# Cap_Sensor_hand.net
KiCad netlist of a schematic drawn in Altium Designer
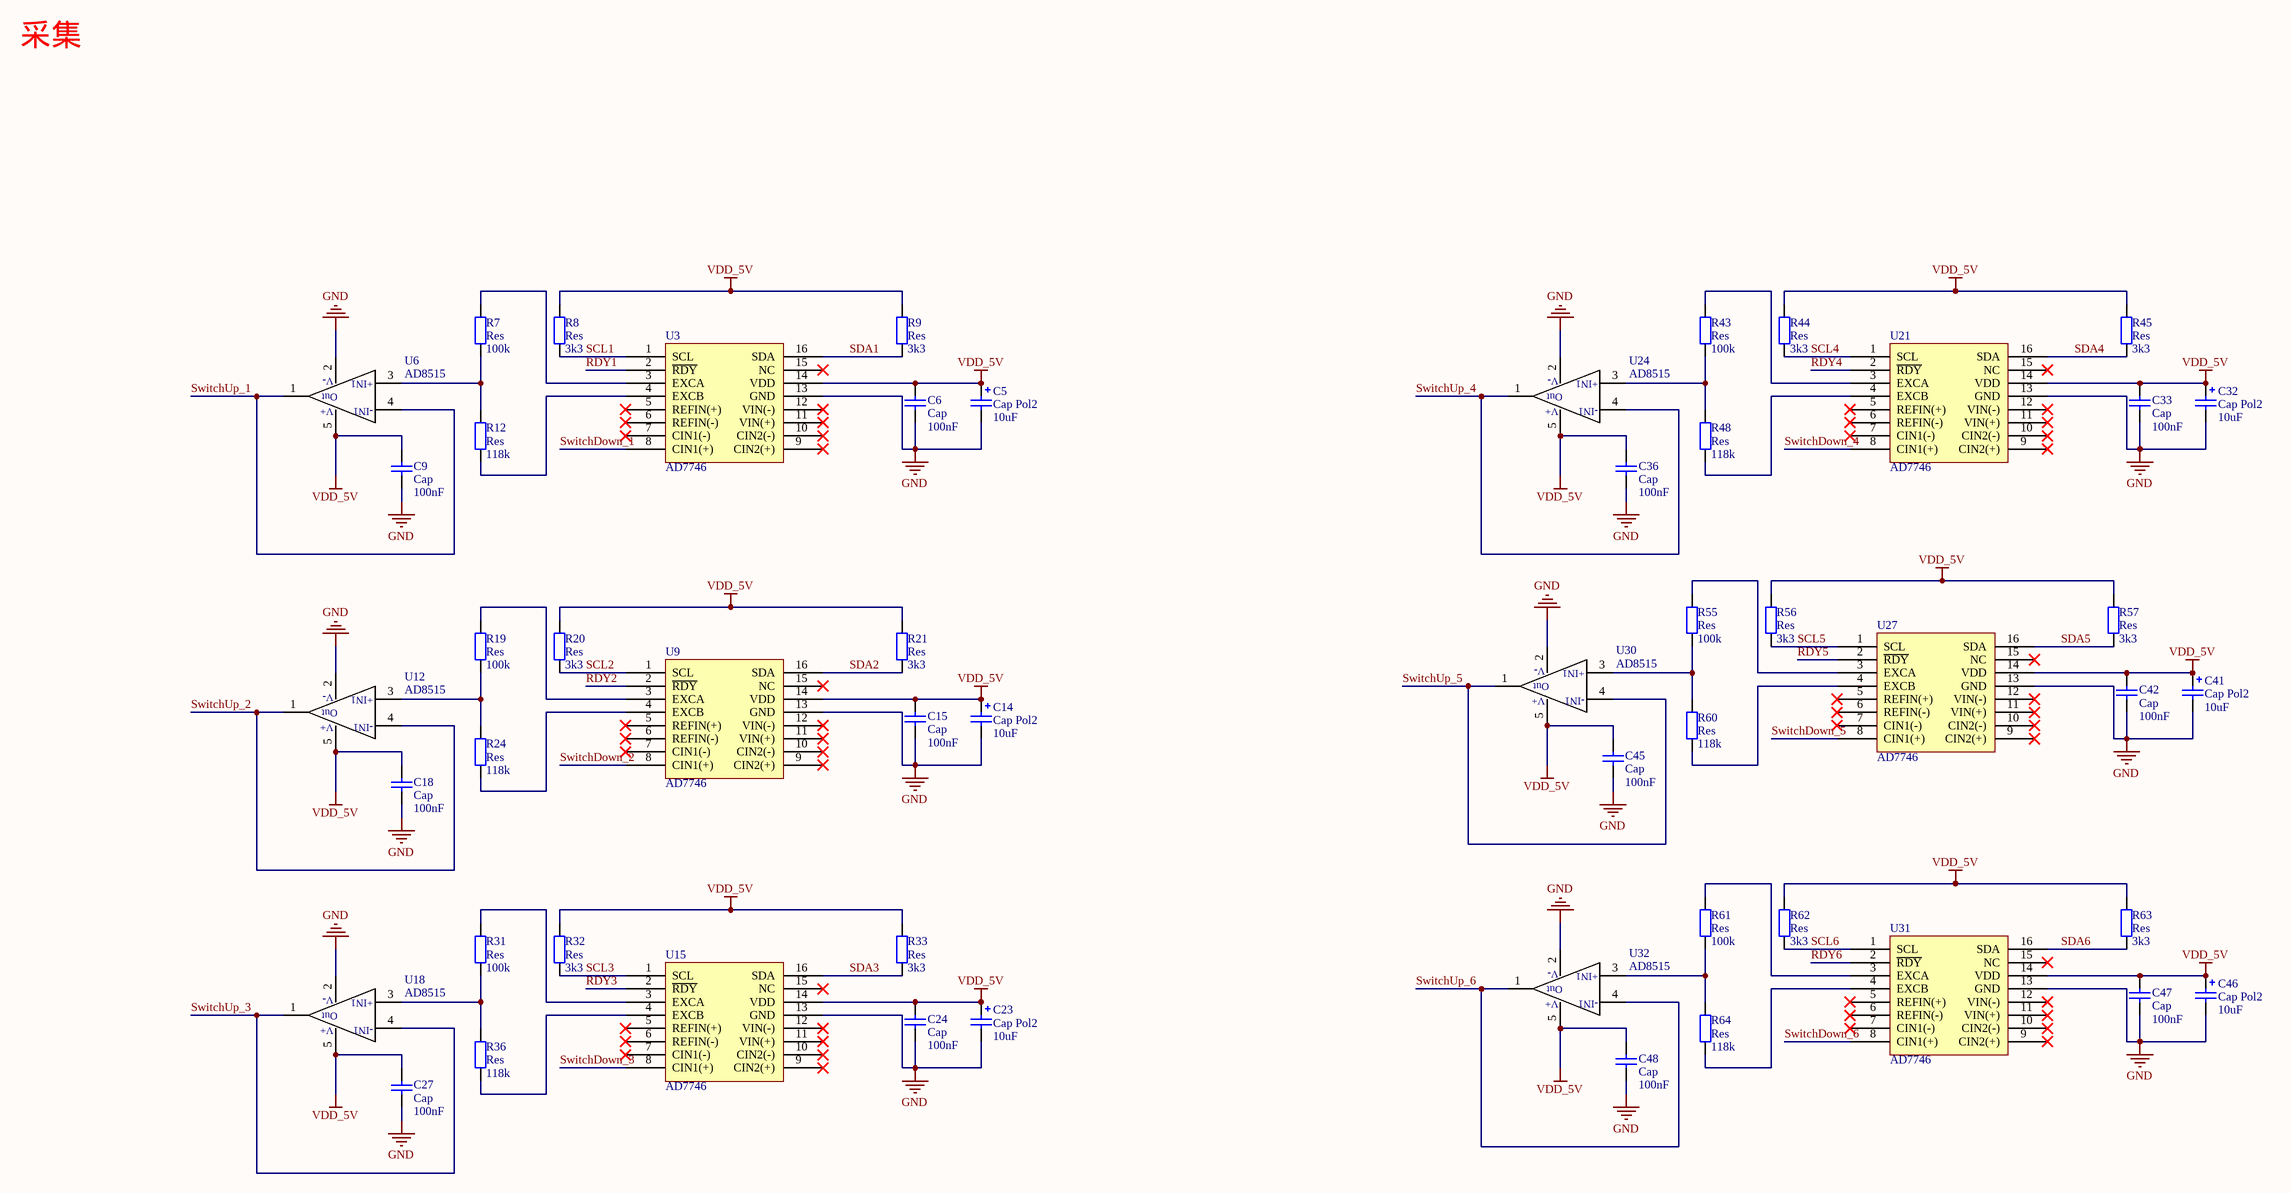
[diagram p0: Cap_Sensor_hand.SchDoc]

(export (version "E")
  (design (tool "Eeschema 10.0.6"))
  (components
    (comp (ref "C5")
      (value "Cap Pol2")
      (footprint "Cap-TA")
      (description "Polarized Capacitor (Axial)")
      (fields (field (name "ALTIUM_VALUE") "10uF") (field (name "PUBLISHER") "Altium Limited"))
      (libsource (lib "YD-LibrarySCH") (part "Cap Pol2"))
    )
    (comp (ref "C6")
      (value "Cap")
      (footprint "0805C")
      (description "Capacitor")
      (fields (field (name "ALTIUM_VALUE") "100nF") (field (name "PUBLISHER") "Altium Limited"))
      (libsource (lib "YD-LibrarySCH") (part "Cap"))
    )
    (comp (ref "C9")
      (value "Cap")
      (footprint "0805C")
      (description "Capacitor")
      (fields (field (name "ALTIUM_VALUE") "100nF") (field (name "PUBLISHER") "Altium Limited"))
      (libsource (lib "YD-LibrarySCH") (part "Cap"))
    )
    (comp (ref "C14")
      (value "Cap Pol2")
      (footprint "Cap-TA")
      (description "Polarized Capacitor (Axial)")
      (fields (field (name "ALTIUM_VALUE") "10uF") (field (name "PUBLISHER") "Altium Limited"))
      (libsource (lib "YD-LibrarySCH") (part "Cap Pol2"))
    )
    (comp (ref "C15")
      (value "Cap")
      (footprint "0805C")
      (description "Capacitor")
      (fields (field (name "ALTIUM_VALUE") "100nF") (field (name "PUBLISHER") "Altium Limited"))
      (libsource (lib "YD-LibrarySCH") (part "Cap"))
    )
    (comp (ref "C18")
      (value "Cap")
      (footprint "0805C")
      (description "Capacitor")
      (fields (field (name "ALTIUM_VALUE") "100nF") (field (name "PUBLISHER") "Altium Limited"))
      (libsource (lib "YD-LibrarySCH") (part "Cap"))
    )
    (comp (ref "C23")
      (value "Cap Pol2")
      (footprint "Cap-TA")
      (description "Polarized Capacitor (Axial)")
      (fields (field (name "ALTIUM_VALUE") "10uF") (field (name "PUBLISHER") "Altium Limited"))
      (libsource (lib "YD-LibrarySCH") (part "Cap Pol2"))
    )
    (comp (ref "C24")
      (value "Cap")
      (footprint "0805C")
      (description "Capacitor")
      (fields (field (name "ALTIUM_VALUE") "100nF") (field (name "PUBLISHER") "Altium Limited"))
      (libsource (lib "YD-LibrarySCH") (part "Cap"))
    )
    (comp (ref "C27")
      (value "Cap")
      (footprint "0805C")
      (description "Capacitor")
      (fields (field (name "ALTIUM_VALUE") "100nF") (field (name "PUBLISHER") "Altium Limited"))
      (libsource (lib "YD-LibrarySCH") (part "Cap"))
    )
    (comp (ref "C32")
      (value "Cap Pol2")
      (footprint "Cap-TA")
      (description "Polarized Capacitor (Axial)")
      (fields (field (name "ALTIUM_VALUE") "10uF") (field (name "PUBLISHER") "Altium Limited"))
      (libsource (lib "YD-LibrarySCH") (part "Cap Pol2"))
    )
    (comp (ref "C33")
      (value "Cap")
      (footprint "0805C")
      (description "Capacitor")
      (fields (field (name "ALTIUM_VALUE") "100nF") (field (name "PUBLISHER") "Altium Limited"))
      (libsource (lib "YD-LibrarySCH") (part "Cap"))
    )
    (comp (ref "C36")
      (value "Cap")
      (footprint "0805C")
      (description "Capacitor")
      (fields (field (name "ALTIUM_VALUE") "100nF") (field (name "PUBLISHER") "Altium Limited"))
      (libsource (lib "YD-LibrarySCH") (part "Cap"))
    )
    (comp (ref "C41")
      (value "Cap Pol2")
      (footprint "Cap-TA")
      (description "Polarized Capacitor (Axial)")
      (fields (field (name "ALTIUM_VALUE") "10uF") (field (name "PUBLISHER") "Altium Limited"))
      (libsource (lib "YD-LibrarySCH") (part "Cap Pol2"))
    )
    (comp (ref "C42")
      (value "Cap")
      (footprint "0805C")
      (description "Capacitor")
      (fields (field (name "ALTIUM_VALUE") "100nF") (field (name "PUBLISHER") "Altium Limited"))
      (libsource (lib "YD-LibrarySCH") (part "Cap"))
    )
    (comp (ref "C45")
      (value "Cap")
      (footprint "0805C")
      (description "Capacitor")
      (fields (field (name "ALTIUM_VALUE") "100nF") (field (name "PUBLISHER") "Altium Limited"))
      (libsource (lib "YD-LibrarySCH") (part "Cap"))
    )
    (comp (ref "C46")
      (value "Cap Pol2")
      (footprint "Cap-TA")
      (description "Polarized Capacitor (Axial)")
      (fields (field (name "ALTIUM_VALUE") "10uF") (field (name "PUBLISHER") "Altium Limited"))
      (libsource (lib "YD-LibrarySCH") (part "Cap Pol2"))
    )
    (comp (ref "C47")
      (value "Cap")
      (footprint "0805C")
      (description "Capacitor")
      (fields (field (name "ALTIUM_VALUE") "100nF") (field (name "PUBLISHER") "Altium Limited"))
      (libsource (lib "YD-LibrarySCH") (part "Cap"))
    )
    (comp (ref "C48")
      (value "Cap")
      (footprint "0805C")
      (description "Capacitor")
      (fields (field (name "ALTIUM_VALUE") "100nF") (field (name "PUBLISHER") "Altium Limited"))
      (libsource (lib "YD-LibrarySCH") (part "Cap"))
    )
    (comp (ref "R7")
      (value "Res")
      (footprint "0805R")
      (description "Resistor")
      (fields (field (name "ALTIUM_VALUE") "100k") (field (name "PUBLISHER") "Altium Limited"))
      (libsource (lib "YD-LibrarySCH") (part "Res"))
    )
    (comp (ref "R8")
      (value "Res")
      (footprint "0805R")
      (description "Resistor")
      (fields (field (name "ALTIUM_VALUE") "3k3") (field (name "PUBLISHER") "Altium Limited"))
      (libsource (lib "") (part "Res_1"))
    )
    (comp (ref "R9")
      (value "Res")
      (footprint "0805R")
      (description "Resistor")
      (fields (field (name "ALTIUM_VALUE") "3k3") (field (name "PUBLISHER") "Altium Limited"))
      (libsource (lib "") (part "Res_1"))
    )
    (comp (ref "R12")
      (value "Res")
      (footprint "0805R")
      (description "Resistor")
      (fields (field (name "ALTIUM_VALUE") "118k") (field (name "PUBLISHER") "Altium Limited"))
      (libsource (lib "YD-LibrarySCH") (part "Res"))
    )
    (comp (ref "R19")
      (value "Res")
      (footprint "0805R")
      (description "Resistor")
      (fields (field (name "ALTIUM_VALUE") "100k") (field (name "PUBLISHER") "Altium Limited"))
      (libsource (lib "YD-LibrarySCH") (part "Res"))
    )
    (comp (ref "R20")
      (value "Res")
      (footprint "0805R")
      (description "Resistor")
      (fields (field (name "ALTIUM_VALUE") "3k3") (field (name "PUBLISHER") "Altium Limited"))
      (libsource (lib "") (part "Res_1"))
    )
    (comp (ref "R21")
      (value "Res")
      (footprint "0805R")
      (description "Resistor")
      (fields (field (name "ALTIUM_VALUE") "3k3") (field (name "PUBLISHER") "Altium Limited"))
      (libsource (lib "") (part "Res_1"))
    )
    (comp (ref "R24")
      (value "Res")
      (footprint "0805R")
      (description "Resistor")
      (fields (field (name "ALTIUM_VALUE") "118k") (field (name "PUBLISHER") "Altium Limited"))
      (libsource (lib "YD-LibrarySCH") (part "Res"))
    )
    (comp (ref "R31")
      (value "Res")
      (footprint "0805R")
      (description "Resistor")
      (fields (field (name "ALTIUM_VALUE") "100k") (field (name "PUBLISHER") "Altium Limited"))
      (libsource (lib "YD-LibrarySCH") (part "Res"))
    )
    (comp (ref "R32")
      (value "Res")
      (footprint "0805R")
      (description "Resistor")
      (fields (field (name "ALTIUM_VALUE") "3k3") (field (name "PUBLISHER") "Altium Limited"))
      (libsource (lib "") (part "Res_1"))
    )
    (comp (ref "R33")
      (value "Res")
      (footprint "0805R")
      (description "Resistor")
      (fields (field (name "ALTIUM_VALUE") "3k3") (field (name "PUBLISHER") "Altium Limited"))
      (libsource (lib "") (part "Res_1"))
    )
    (comp (ref "R36")
      (value "Res")
      (footprint "0805R")
      (description "Resistor")
      (fields (field (name "ALTIUM_VALUE") "118k") (field (name "PUBLISHER") "Altium Limited"))
      (libsource (lib "YD-LibrarySCH") (part "Res"))
    )
    (comp (ref "R43")
      (value "Res")
      (footprint "0805R")
      (description "Resistor")
      (fields (field (name "ALTIUM_VALUE") "100k") (field (name "PUBLISHER") "Altium Limited"))
      (libsource (lib "YD-LibrarySCH") (part "Res"))
    )
    (comp (ref "R44")
      (value "Res")
      (footprint "0805R")
      (description "Resistor")
      (fields (field (name "ALTIUM_VALUE") "3k3") (field (name "PUBLISHER") "Altium Limited"))
      (libsource (lib "") (part "Res_1"))
    )
    (comp (ref "R45")
      (value "Res")
      (footprint "0805R")
      (description "Resistor")
      (fields (field (name "ALTIUM_VALUE") "3k3") (field (name "PUBLISHER") "Altium Limited"))
      (libsource (lib "") (part "Res_1"))
    )
    (comp (ref "R48")
      (value "Res")
      (footprint "0805R")
      (description "Resistor")
      (fields (field (name "ALTIUM_VALUE") "118k") (field (name "PUBLISHER") "Altium Limited"))
      (libsource (lib "YD-LibrarySCH") (part "Res"))
    )
    (comp (ref "R55")
      (value "Res")
      (footprint "0805R")
      (description "Resistor")
      (fields (field (name "ALTIUM_VALUE") "100k") (field (name "PUBLISHER") "Altium Limited"))
      (libsource (lib "YD-LibrarySCH") (part "Res"))
    )
    (comp (ref "R56")
      (value "Res")
      (footprint "0805R")
      (description "Resistor")
      (fields (field (name "ALTIUM_VALUE") "3k3") (field (name "PUBLISHER") "Altium Limited"))
      (libsource (lib "") (part "Res_1"))
    )
    (comp (ref "R57")
      (value "Res")
      (footprint "0805R")
      (description "Resistor")
      (fields (field (name "ALTIUM_VALUE") "3k3") (field (name "PUBLISHER") "Altium Limited"))
      (libsource (lib "") (part "Res_1"))
    )
    (comp (ref "R60")
      (value "Res")
      (footprint "0805R")
      (description "Resistor")
      (fields (field (name "ALTIUM_VALUE") "118k") (field (name "PUBLISHER") "Altium Limited"))
      (libsource (lib "YD-LibrarySCH") (part "Res"))
    )
    (comp (ref "R61")
      (value "Res")
      (footprint "0805R")
      (description "Resistor")
      (fields (field (name "ALTIUM_VALUE") "100k") (field (name "PUBLISHER") "Altium Limited"))
      (libsource (lib "YD-LibrarySCH") (part "Res"))
    )
    (comp (ref "R62")
      (value "Res")
      (footprint "0805R")
      (description "Resistor")
      (fields (field (name "ALTIUM_VALUE") "3k3") (field (name "PUBLISHER") "Altium Limited"))
      (libsource (lib "") (part "Res_1"))
    )
    (comp (ref "R63")
      (value "Res")
      (footprint "0805R")
      (description "Resistor")
      (fields (field (name "ALTIUM_VALUE") "3k3") (field (name "PUBLISHER") "Altium Limited"))
      (libsource (lib "") (part "Res_1"))
    )
    (comp (ref "R64")
      (value "Res")
      (footprint "0805R")
      (description "Resistor")
      (fields (field (name "ALTIUM_VALUE") "118k") (field (name "PUBLISHER") "Altium Limited"))
      (libsource (lib "YD-LibrarySCH") (part "Res"))
    )
    (comp (ref "U3") (value "AD7746") (footprint "TSSOP16") (libsource (lib "YD-LibrarySCH") (part "AD7746")))
    (comp (ref "U6") (value "AD8515") (footprint "sot23-5") (libsource (lib "YD-LibrarySCH") (part "AD8515")))
    (comp (ref "U9") (value "AD7746") (footprint "TSSOP16") (libsource (lib "YD-LibrarySCH") (part "AD7746")))
    (comp (ref "U12")
      (value "AD8515")
      (footprint "sot23-5")
      (libsource (lib "YD-LibrarySCH") (part "AD8515"))
    )
    (comp (ref "U15")
      (value "AD7746")
      (footprint "TSSOP16")
      (libsource (lib "YD-LibrarySCH") (part "AD7746"))
    )
    (comp (ref "U18")
      (value "AD8515")
      (footprint "sot23-5")
      (libsource (lib "YD-LibrarySCH") (part "AD8515"))
    )
    (comp (ref "U21")
      (value "AD7746")
      (footprint "TSSOP16")
      (libsource (lib "YD-LibrarySCH") (part "AD7746"))
    )
    (comp (ref "U24")
      (value "AD8515")
      (footprint "sot23-5")
      (libsource (lib "YD-LibrarySCH") (part "AD8515"))
    )
    (comp (ref "U27")
      (value "AD7746")
      (footprint "TSSOP16")
      (libsource (lib "YD-LibrarySCH") (part "AD7746"))
    )
    (comp (ref "U30")
      (value "AD8515")
      (footprint "sot23-5")
      (libsource (lib "YD-LibrarySCH") (part "AD8515"))
    )
    (comp (ref "U31")
      (value "AD7746")
      (footprint "TSSOP16")
      (libsource (lib "YD-LibrarySCH") (part "AD7746"))
    )
    (comp (ref "U32")
      (value "AD8515")
      (footprint "sot23-5")
      (libsource (lib "YD-LibrarySCH") (part "AD8515"))
    )
  )
  (nets
    (net (code "1") (name "/RDY1") (class "Default")
      (node (ref "U3") (pin "2") (pinfunction "~{RDY}_2") (pintype "passive"))
    )
    (net (code "2") (name "/RDY2") (class "Default")
      (node (ref "U9") (pin "2") (pinfunction "~{RDY}_2") (pintype "passive"))
    )
    (net (code "3") (name "/RDY3") (class "Default")
      (node (ref "U15") (pin "2") (pinfunction "~{RDY}_2") (pintype "passive"))
    )
    (net (code "4") (name "/RDY4") (class "Default")
      (node (ref "U21") (pin "2") (pinfunction "~{RDY}_2") (pintype "passive"))
    )
    (net (code "5") (name "/RDY5") (class "Default")
      (node (ref "U27") (pin "2") (pinfunction "~{RDY}_2") (pintype "passive"))
    )
    (net (code "6") (name "/RDY6") (class "Default")
      (node (ref "U31") (pin "2") (pinfunction "~{RDY}_2") (pintype "passive"))
    )
    (net (code "7") (name "/SCL1") (class "Default")
      (node (ref "R8") (pin "1") (pinfunction "1_1") (pintype "passive"))
      (node (ref "U3") (pin "1") (pinfunction "SCL_1") (pintype "passive"))
    )
    (net (code "8") (name "/SCL2") (class "Default")
      (node (ref "R20") (pin "1") (pinfunction "1_1") (pintype "passive"))
      (node (ref "U9") (pin "1") (pinfunction "SCL_1") (pintype "passive"))
    )
    (net (code "9") (name "/SCL3") (class "Default")
      (node (ref "R32") (pin "1") (pinfunction "1_1") (pintype "passive"))
      (node (ref "U15") (pin "1") (pinfunction "SCL_1") (pintype "passive"))
    )
    (net (code "10") (name "/SCL4") (class "Default")
      (node (ref "R44") (pin "1") (pinfunction "1_1") (pintype "passive"))
      (node (ref "U21") (pin "1") (pinfunction "SCL_1") (pintype "passive"))
    )
    (net (code "11") (name "/SCL5") (class "Default")
      (node (ref "R56") (pin "1") (pinfunction "1_1") (pintype "passive"))
      (node (ref "U27") (pin "1") (pinfunction "SCL_1") (pintype "passive"))
    )
    (net (code "12") (name "/SCL6") (class "Default")
      (node (ref "R62") (pin "1") (pinfunction "1_1") (pintype "passive"))
      (node (ref "U31") (pin "1") (pinfunction "SCL_1") (pintype "passive"))
    )
    (net (code "13") (name "/SDA1") (class "Default")
      (node (ref "R9") (pin "1") (pinfunction "1_1") (pintype "passive"))
      (node (ref "U3") (pin "16") (pinfunction "SDA_16") (pintype "passive"))
    )
    (net (code "14") (name "/SDA2") (class "Default")
      (node (ref "R21") (pin "1") (pinfunction "1_1") (pintype "passive"))
      (node (ref "U9") (pin "16") (pinfunction "SDA_16") (pintype "passive"))
    )
    (net (code "15") (name "/SDA3") (class "Default")
      (node (ref "R33") (pin "1") (pinfunction "1_1") (pintype "passive"))
      (node (ref "U15") (pin "16") (pinfunction "SDA_16") (pintype "passive"))
    )
    (net (code "16") (name "/SDA4") (class "Default")
      (node (ref "R45") (pin "1") (pinfunction "1_1") (pintype "passive"))
      (node (ref "U21") (pin "16") (pinfunction "SDA_16") (pintype "passive"))
    )
    (net (code "17") (name "/SDA5") (class "Default")
      (node (ref "R57") (pin "1") (pinfunction "1_1") (pintype "passive"))
      (node (ref "U27") (pin "16") (pinfunction "SDA_16") (pintype "passive"))
    )
    (net (code "18") (name "/SDA6") (class "Default")
      (node (ref "R63") (pin "1") (pinfunction "1_1") (pintype "passive"))
      (node (ref "U31") (pin "16") (pinfunction "SDA_16") (pintype "passive"))
    )
    (net (code "19") (name "/SwitchDown_1") (class "Default")
      (node (ref "U3") (pin "8") (pinfunction "CIN1(+)_8") (pintype "passive"))
    )
    (net (code "20") (name "/SwitchDown_2") (class "Default")
      (node (ref "U9") (pin "8") (pinfunction "CIN1(+)_8") (pintype "passive"))
    )
    (net (code "21") (name "/SwitchDown_3") (class "Default")
      (node (ref "U15") (pin "8") (pinfunction "CIN1(+)_8") (pintype "passive"))
    )
    (net (code "22") (name "/SwitchDown_4") (class "Default")
      (node (ref "U21") (pin "8") (pinfunction "CIN1(+)_8") (pintype "passive"))
    )
    (net (code "23") (name "/SwitchDown_5") (class "Default")
      (node (ref "U27") (pin "8") (pinfunction "CIN1(+)_8") (pintype "passive"))
    )
    (net (code "24") (name "/SwitchDown_6") (class "Default")
      (node (ref "U31") (pin "8") (pinfunction "CIN1(+)_8") (pintype "passive"))
    )
    (net (code "25") (name "/SwitchUp_1") (class "Default")
      (node (ref "U6") (pin "1") (pinfunction "Out1_1") (pintype "passive"))
      (node (ref "U6") (pin "4") (pinfunction "-IN_4") (pintype "passive"))
    )
    (net (code "26") (name "/SwitchUp_2") (class "Default")
      (node (ref "U12") (pin "1") (pinfunction "Out1_1") (pintype "passive"))
      (node (ref "U12") (pin "4") (pinfunction "-IN_4") (pintype "passive"))
    )
    (net (code "27") (name "/SwitchUp_3") (class "Default")
      (node (ref "U18") (pin "1") (pinfunction "Out1_1") (pintype "passive"))
      (node (ref "U18") (pin "4") (pinfunction "-IN_4") (pintype "passive"))
    )
    (net (code "28") (name "/SwitchUp_4") (class "Default")
      (node (ref "U24") (pin "1") (pinfunction "Out1_1") (pintype "passive"))
      (node (ref "U24") (pin "4") (pinfunction "-IN_4") (pintype "passive"))
    )
    (net (code "29") (name "/SwitchUp_5") (class "Default")
      (node (ref "U30") (pin "1") (pinfunction "Out1_1") (pintype "passive"))
      (node (ref "U30") (pin "4") (pinfunction "-IN_4") (pintype "passive"))
    )
    (net (code "30") (name "/SwitchUp_6") (class "Default")
      (node (ref "U32") (pin "1") (pinfunction "Out1_1") (pintype "passive"))
      (node (ref "U32") (pin "4") (pinfunction "-IN_4") (pintype "passive"))
    )
    (net (code "32") (name "GND") (class "Default")
      (node (ref "C14") (pin "2") (pinfunction "2_2") (pintype "passive"))
      (node (ref "C15") (pin "1") (pinfunction "1_1") (pintype "passive"))
      (node (ref "C18") (pin "1") (pinfunction "1_1") (pintype "passive"))
      (node (ref "C23") (pin "2") (pinfunction "2_2") (pintype "passive"))
      (node (ref "C24") (pin "1") (pinfunction "1_1") (pintype "passive"))
      (node (ref "C27") (pin "1") (pinfunction "1_1") (pintype "passive"))
      (node (ref "C32") (pin "2") (pinfunction "2_2") (pintype "passive"))
      (node (ref "C33") (pin "1") (pinfunction "1_1") (pintype "passive"))
      (node (ref "C36") (pin "1") (pinfunction "1_1") (pintype "passive"))
      (node (ref "C41") (pin "2") (pinfunction "2_2") (pintype "passive"))
      (node (ref "C42") (pin "1") (pinfunction "1_1") (pintype "passive"))
      (node (ref "C45") (pin "1") (pinfunction "1_1") (pintype "passive"))
      (node (ref "C46") (pin "2") (pinfunction "2_2") (pintype "passive"))
      (node (ref "C47") (pin "1") (pinfunction "1_1") (pintype "passive"))
      (node (ref "C48") (pin "1") (pinfunction "1_1") (pintype "passive"))
      (node (ref "C5") (pin "2") (pinfunction "2_2") (pintype "passive"))
      (node (ref "C6") (pin "1") (pinfunction "1_1") (pintype "passive"))
      (node (ref "C9") (pin "1") (pinfunction "1_1") (pintype "passive"))
      (node (ref "U12") (pin "2") (pinfunction "V-_2") (pintype "passive"))
      (node (ref "U15") (pin "13") (pinfunction "GND_13") (pintype "passive"))
      (node (ref "U18") (pin "2") (pinfunction "V-_2") (pintype "passive"))
      (node (ref "U21") (pin "13") (pinfunction "GND_13") (pintype "passive"))
      (node (ref "U24") (pin "2") (pinfunction "V-_2") (pintype "passive"))
      (node (ref "U27") (pin "13") (pinfunction "GND_13") (pintype "passive"))
      (node (ref "U3") (pin "13") (pinfunction "GND_13") (pintype "passive"))
      (node (ref "U30") (pin "2") (pinfunction "V-_2") (pintype "passive"))
      (node (ref "U31") (pin "13") (pinfunction "GND_13") (pintype "passive"))
      (node (ref "U32") (pin "2") (pinfunction "V-_2") (pintype "passive"))
      (node (ref "U6") (pin "2") (pinfunction "V-_2") (pintype "passive"))
      (node (ref "U9") (pin "13") (pinfunction "GND_13") (pintype "passive"))
    )
    (net (code "33") (name "Net-(U3-EXCA)") (class "Default")
      (node (ref "R7") (pin "1") (pinfunction "1_1") (pintype "passive"))
      (node (ref "U3") (pin "3") (pinfunction "EXCA_3") (pintype "passive"))
    )
    (net (code "34") (name "Net-(U3-EXCB)") (class "Default")
      (node (ref "R12") (pin "2") (pinfunction "2_2") (pintype "passive"))
      (node (ref "U3") (pin "4") (pinfunction "EXCB_4") (pintype "passive"))
    )
    (net (code "35") (name "Net-(U6-+IN)") (class "Default")
      (node (ref "R12") (pin "1") (pinfunction "1_1") (pintype "passive"))
      (node (ref "R7") (pin "2") (pinfunction "2_2") (pintype "passive"))
      (node (ref "U6") (pin "3") (pinfunction "+IN_3") (pintype "passive"))
    )
    (net (code "36") (name "Net-(U9-EXCA)") (class "Default")
      (node (ref "R19") (pin "1") (pinfunction "1_1") (pintype "passive"))
      (node (ref "U9") (pin "3") (pinfunction "EXCA_3") (pintype "passive"))
    )
    (net (code "37") (name "Net-(U9-EXCB)") (class "Default")
      (node (ref "R24") (pin "2") (pinfunction "2_2") (pintype "passive"))
      (node (ref "U9") (pin "4") (pinfunction "EXCB_4") (pintype "passive"))
    )
    (net (code "38") (name "Net-(U12-+IN)") (class "Default")
      (node (ref "R19") (pin "2") (pinfunction "2_2") (pintype "passive"))
      (node (ref "R24") (pin "1") (pinfunction "1_1") (pintype "passive"))
      (node (ref "U12") (pin "3") (pinfunction "+IN_3") (pintype "passive"))
    )
    (net (code "39") (name "Net-(U15-EXCA)") (class "Default")
      (node (ref "R31") (pin "1") (pinfunction "1_1") (pintype "passive"))
      (node (ref "U15") (pin "3") (pinfunction "EXCA_3") (pintype "passive"))
    )
    (net (code "40") (name "Net-(U15-EXCB)") (class "Default")
      (node (ref "R36") (pin "2") (pinfunction "2_2") (pintype "passive"))
      (node (ref "U15") (pin "4") (pinfunction "EXCB_4") (pintype "passive"))
    )
    (net (code "41") (name "Net-(U18-+IN)") (class "Default")
      (node (ref "R31") (pin "2") (pinfunction "2_2") (pintype "passive"))
      (node (ref "R36") (pin "1") (pinfunction "1_1") (pintype "passive"))
      (node (ref "U18") (pin "3") (pinfunction "+IN_3") (pintype "passive"))
    )
    (net (code "42") (name "Net-(U21-EXCA)") (class "Default")
      (node (ref "R43") (pin "1") (pinfunction "1_1") (pintype "passive"))
      (node (ref "U21") (pin "3") (pinfunction "EXCA_3") (pintype "passive"))
    )
    (net (code "43") (name "Net-(U21-EXCB)") (class "Default")
      (node (ref "R48") (pin "2") (pinfunction "2_2") (pintype "passive"))
      (node (ref "U21") (pin "4") (pinfunction "EXCB_4") (pintype "passive"))
    )
    (net (code "44") (name "Net-(U24-+IN)") (class "Default")
      (node (ref "R43") (pin "2") (pinfunction "2_2") (pintype "passive"))
      (node (ref "R48") (pin "1") (pinfunction "1_1") (pintype "passive"))
      (node (ref "U24") (pin "3") (pinfunction "+IN_3") (pintype "passive"))
    )
    (net (code "45") (name "Net-(U27-EXCA)") (class "Default")
      (node (ref "R55") (pin "1") (pinfunction "1_1") (pintype "passive"))
      (node (ref "U27") (pin "3") (pinfunction "EXCA_3") (pintype "passive"))
    )
    (net (code "46") (name "Net-(U27-EXCB)") (class "Default")
      (node (ref "R60") (pin "2") (pinfunction "2_2") (pintype "passive"))
      (node (ref "U27") (pin "4") (pinfunction "EXCB_4") (pintype "passive"))
    )
    (net (code "47") (name "Net-(U30-+IN)") (class "Default")
      (node (ref "R55") (pin "2") (pinfunction "2_2") (pintype "passive"))
      (node (ref "R60") (pin "1") (pinfunction "1_1") (pintype "passive"))
      (node (ref "U30") (pin "3") (pinfunction "+IN_3") (pintype "passive"))
    )
    (net (code "48") (name "Net-(U31-EXCA)") (class "Default")
      (node (ref "R61") (pin "1") (pinfunction "1_1") (pintype "passive"))
      (node (ref "U31") (pin "3") (pinfunction "EXCA_3") (pintype "passive"))
    )
    (net (code "49") (name "Net-(U31-EXCB)") (class "Default")
      (node (ref "R64") (pin "2") (pinfunction "2_2") (pintype "passive"))
      (node (ref "U31") (pin "4") (pinfunction "EXCB_4") (pintype "passive"))
    )
    (net (code "50") (name "Net-(U32-+IN)") (class "Default")
      (node (ref "R61") (pin "2") (pinfunction "2_2") (pintype "passive"))
      (node (ref "R64") (pin "1") (pinfunction "1_1") (pintype "passive"))
      (node (ref "U32") (pin "3") (pinfunction "+IN_3") (pintype "passive"))
    )
    (net (code "51") (name "VDD_5V") (class "Default")
      (node (ref "C14") (pin "1") (pinfunction "1_1") (pintype "passive"))
      (node (ref "C15") (pin "2") (pinfunction "2_2") (pintype "passive"))
      (node (ref "C18") (pin "2") (pinfunction "2_2") (pintype "passive"))
      (node (ref "C23") (pin "1") (pinfunction "1_1") (pintype "passive"))
      (node (ref "C24") (pin "2") (pinfunction "2_2") (pintype "passive"))
      (node (ref "C27") (pin "2") (pinfunction "2_2") (pintype "passive"))
      (node (ref "C32") (pin "1") (pinfunction "1_1") (pintype "passive"))
      (node (ref "C33") (pin "2") (pinfunction "2_2") (pintype "passive"))
      (node (ref "C36") (pin "2") (pinfunction "2_2") (pintype "passive"))
      (node (ref "C41") (pin "1") (pinfunction "1_1") (pintype "passive"))
      (node (ref "C42") (pin "2") (pinfunction "2_2") (pintype "passive"))
      (node (ref "C45") (pin "2") (pinfunction "2_2") (pintype "passive"))
      (node (ref "C46") (pin "1") (pinfunction "1_1") (pintype "passive"))
      (node (ref "C47") (pin "2") (pinfunction "2_2") (pintype "passive"))
      (node (ref "C48") (pin "2") (pinfunction "2_2") (pintype "passive"))
      (node (ref "C5") (pin "1") (pinfunction "1_1") (pintype "passive"))
      (node (ref "C6") (pin "2") (pinfunction "2_2") (pintype "passive"))
      (node (ref "C9") (pin "2") (pinfunction "2_2") (pintype "passive"))
      (node (ref "R20") (pin "2") (pinfunction "2_2") (pintype "passive"))
      (node (ref "R21") (pin "2") (pinfunction "2_2") (pintype "passive"))
      (node (ref "R32") (pin "2") (pinfunction "2_2") (pintype "passive"))
      (node (ref "R33") (pin "2") (pinfunction "2_2") (pintype "passive"))
      (node (ref "R44") (pin "2") (pinfunction "2_2") (pintype "passive"))
      (node (ref "R45") (pin "2") (pinfunction "2_2") (pintype "passive"))
      (node (ref "R56") (pin "2") (pinfunction "2_2") (pintype "passive"))
      (node (ref "R57") (pin "2") (pinfunction "2_2") (pintype "passive"))
      (node (ref "R62") (pin "2") (pinfunction "2_2") (pintype "passive"))
      (node (ref "R63") (pin "2") (pinfunction "2_2") (pintype "passive"))
      (node (ref "R8") (pin "2") (pinfunction "2_2") (pintype "passive"))
      (node (ref "R9") (pin "2") (pinfunction "2_2") (pintype "passive"))
      (node (ref "U12") (pin "5") (pinfunction "V+_5") (pintype "passive"))
      (node (ref "U15") (pin "14") (pinfunction "VDD_14") (pintype "passive"))
      (node (ref "U18") (pin "5") (pinfunction "V+_5") (pintype "passive"))
      (node (ref "U21") (pin "14") (pinfunction "VDD_14") (pintype "passive"))
      (node (ref "U24") (pin "5") (pinfunction "V+_5") (pintype "passive"))
      (node (ref "U27") (pin "14") (pinfunction "VDD_14") (pintype "passive"))
      (node (ref "U3") (pin "14") (pinfunction "VDD_14") (pintype "passive"))
      (node (ref "U30") (pin "5") (pinfunction "V+_5") (pintype "passive"))
      (node (ref "U31") (pin "14") (pinfunction "VDD_14") (pintype "passive"))
      (node (ref "U32") (pin "5") (pinfunction "V+_5") (pintype "passive"))
      (node (ref "U6") (pin "5") (pinfunction "V+_5") (pintype "passive"))
      (node (ref "U9") (pin "14") (pinfunction "VDD_14") (pintype "passive"))
    )
    (net (code "52") (name "unconnected-(U3-CIN1(-)-Pad7)") (class "Default")
      (node (ref "U3") (pin "7") (pinfunction "CIN1(-)_7") (pintype "passive+no_connect"))
    )
    (net (code "53") (name "unconnected-(U3-CIN2(+)-Pad9)") (class "Default")
      (node (ref "U3") (pin "9") (pinfunction "CIN2(+)_9") (pintype "passive+no_connect"))
    )
    (net (code "54") (name "unconnected-(U3-CIN2(-)-Pad10)") (class "Default")
      (node (ref "U3") (pin "10") (pinfunction "CIN2(-)_10") (pintype "passive+no_connect"))
    )
    (net (code "55") (name "unconnected-(U3-NC-Pad15)") (class "Default")
      (node (ref "U3") (pin "15") (pinfunction "NC_15") (pintype "passive+no_connect"))
    )
    (net (code "56") (name "unconnected-(U3-REFIN(+)-Pad5)") (class "Default")
      (node (ref "U3") (pin "5") (pinfunction "REFIN(+)_5") (pintype "passive+no_connect"))
    )
    (net (code "57") (name "unconnected-(U3-REFIN(-)-Pad6)") (class "Default")
      (node (ref "U3") (pin "6") (pinfunction "REFIN(-)_6") (pintype "passive+no_connect"))
    )
    (net (code "58") (name "unconnected-(U3-VIN(+)-Pad11)") (class "Default")
      (node (ref "U3") (pin "11") (pinfunction "VIN(+)_11") (pintype "passive+no_connect"))
    )
    (net (code "59") (name "unconnected-(U3-VIN(-)-Pad12)") (class "Default")
      (node (ref "U3") (pin "12") (pinfunction "VIN(-)_12") (pintype "passive+no_connect"))
    )
    (net (code "60") (name "unconnected-(U9-CIN1(-)-Pad7)") (class "Default")
      (node (ref "U9") (pin "7") (pinfunction "CIN1(-)_7") (pintype "passive+no_connect"))
    )
    (net (code "61") (name "unconnected-(U9-CIN2(+)-Pad9)") (class "Default")
      (node (ref "U9") (pin "9") (pinfunction "CIN2(+)_9") (pintype "passive+no_connect"))
    )
    (net (code "62") (name "unconnected-(U9-CIN2(-)-Pad10)") (class "Default")
      (node (ref "U9") (pin "10") (pinfunction "CIN2(-)_10") (pintype "passive+no_connect"))
    )
    (net (code "63") (name "unconnected-(U9-NC-Pad15)") (class "Default")
      (node (ref "U9") (pin "15") (pinfunction "NC_15") (pintype "passive+no_connect"))
    )
    (net (code "64") (name "unconnected-(U9-REFIN(+)-Pad5)") (class "Default")
      (node (ref "U9") (pin "5") (pinfunction "REFIN(+)_5") (pintype "passive+no_connect"))
    )
    (net (code "65") (name "unconnected-(U9-REFIN(-)-Pad6)") (class "Default")
      (node (ref "U9") (pin "6") (pinfunction "REFIN(-)_6") (pintype "passive+no_connect"))
    )
    (net (code "66") (name "unconnected-(U9-VIN(+)-Pad11)") (class "Default")
      (node (ref "U9") (pin "11") (pinfunction "VIN(+)_11") (pintype "passive+no_connect"))
    )
    (net (code "67") (name "unconnected-(U9-VIN(-)-Pad12)") (class "Default")
      (node (ref "U9") (pin "12") (pinfunction "VIN(-)_12") (pintype "passive+no_connect"))
    )
    (net (code "68") (name "unconnected-(U15-CIN1(-)-Pad7)") (class "Default")
      (node (ref "U15") (pin "7") (pinfunction "CIN1(-)_7") (pintype "passive+no_connect"))
    )
    (net (code "69") (name "unconnected-(U15-CIN2(+)-Pad9)") (class "Default")
      (node (ref "U15") (pin "9") (pinfunction "CIN2(+)_9") (pintype "passive+no_connect"))
    )
    (net (code "70") (name "unconnected-(U15-CIN2(-)-Pad10)") (class "Default")
      (node (ref "U15") (pin "10") (pinfunction "CIN2(-)_10") (pintype "passive+no_connect"))
    )
    (net (code "71") (name "unconnected-(U15-NC-Pad15)") (class "Default")
      (node (ref "U15") (pin "15") (pinfunction "NC_15") (pintype "passive+no_connect"))
    )
    (net (code "72") (name "unconnected-(U15-REFIN(+)-Pad5)") (class "Default")
      (node (ref "U15") (pin "5") (pinfunction "REFIN(+)_5") (pintype "passive+no_connect"))
    )
    (net (code "73") (name "unconnected-(U15-REFIN(-)-Pad6)") (class "Default")
      (node (ref "U15") (pin "6") (pinfunction "REFIN(-)_6") (pintype "passive+no_connect"))
    )
    (net (code "74") (name "unconnected-(U15-VIN(+)-Pad11)") (class "Default")
      (node (ref "U15") (pin "11") (pinfunction "VIN(+)_11") (pintype "passive+no_connect"))
    )
    (net (code "75") (name "unconnected-(U15-VIN(-)-Pad12)") (class "Default")
      (node (ref "U15") (pin "12") (pinfunction "VIN(-)_12") (pintype "passive+no_connect"))
    )
    (net (code "76") (name "unconnected-(U21-CIN1(-)-Pad7)") (class "Default")
      (node (ref "U21") (pin "7") (pinfunction "CIN1(-)_7") (pintype "passive+no_connect"))
    )
    (net (code "77") (name "unconnected-(U21-CIN2(+)-Pad9)") (class "Default")
      (node (ref "U21") (pin "9") (pinfunction "CIN2(+)_9") (pintype "passive+no_connect"))
    )
    (net (code "78") (name "unconnected-(U21-CIN2(-)-Pad10)") (class "Default")
      (node (ref "U21") (pin "10") (pinfunction "CIN2(-)_10") (pintype "passive+no_connect"))
    )
    (net (code "79") (name "unconnected-(U21-NC-Pad15)") (class "Default")
      (node (ref "U21") (pin "15") (pinfunction "NC_15") (pintype "passive+no_connect"))
    )
    (net (code "80") (name "unconnected-(U21-REFIN(+)-Pad5)") (class "Default")
      (node (ref "U21") (pin "5") (pinfunction "REFIN(+)_5") (pintype "passive+no_connect"))
    )
    (net (code "81") (name "unconnected-(U21-REFIN(-)-Pad6)") (class "Default")
      (node (ref "U21") (pin "6") (pinfunction "REFIN(-)_6") (pintype "passive+no_connect"))
    )
    (net (code "82") (name "unconnected-(U21-VIN(+)-Pad11)") (class "Default")
      (node (ref "U21") (pin "11") (pinfunction "VIN(+)_11") (pintype "passive+no_connect"))
    )
    (net (code "83") (name "unconnected-(U21-VIN(-)-Pad12)") (class "Default")
      (node (ref "U21") (pin "12") (pinfunction "VIN(-)_12") (pintype "passive+no_connect"))
    )
    (net (code "84") (name "unconnected-(U27-CIN1(-)-Pad7)") (class "Default")
      (node (ref "U27") (pin "7") (pinfunction "CIN1(-)_7") (pintype "passive+no_connect"))
    )
    (net (code "85") (name "unconnected-(U27-CIN2(+)-Pad9)") (class "Default")
      (node (ref "U27") (pin "9") (pinfunction "CIN2(+)_9") (pintype "passive+no_connect"))
    )
    (net (code "86") (name "unconnected-(U27-CIN2(-)-Pad10)") (class "Default")
      (node (ref "U27") (pin "10") (pinfunction "CIN2(-)_10") (pintype "passive+no_connect"))
    )
    (net (code "87") (name "unconnected-(U27-NC-Pad15)") (class "Default")
      (node (ref "U27") (pin "15") (pinfunction "NC_15") (pintype "passive+no_connect"))
    )
    (net (code "88") (name "unconnected-(U27-REFIN(+)-Pad5)") (class "Default")
      (node (ref "U27") (pin "5") (pinfunction "REFIN(+)_5") (pintype "passive+no_connect"))
    )
    (net (code "89") (name "unconnected-(U27-REFIN(-)-Pad6)") (class "Default")
      (node (ref "U27") (pin "6") (pinfunction "REFIN(-)_6") (pintype "passive+no_connect"))
    )
    (net (code "90") (name "unconnected-(U27-VIN(+)-Pad11)") (class "Default")
      (node (ref "U27") (pin "11") (pinfunction "VIN(+)_11") (pintype "passive+no_connect"))
    )
    (net (code "91") (name "unconnected-(U27-VIN(-)-Pad12)") (class "Default")
      (node (ref "U27") (pin "12") (pinfunction "VIN(-)_12") (pintype "passive+no_connect"))
    )
    (net (code "92") (name "unconnected-(U31-CIN1(-)-Pad7)") (class "Default")
      (node (ref "U31") (pin "7") (pinfunction "CIN1(-)_7") (pintype "passive+no_connect"))
    )
    (net (code "93") (name "unconnected-(U31-CIN2(+)-Pad9)") (class "Default")
      (node (ref "U31") (pin "9") (pinfunction "CIN2(+)_9") (pintype "passive+no_connect"))
    )
    (net (code "94") (name "unconnected-(U31-CIN2(-)-Pad10)") (class "Default")
      (node (ref "U31") (pin "10") (pinfunction "CIN2(-)_10") (pintype "passive+no_connect"))
    )
    (net (code "95") (name "unconnected-(U31-NC-Pad15)") (class "Default")
      (node (ref "U31") (pin "15") (pinfunction "NC_15") (pintype "passive+no_connect"))
    )
    (net (code "96") (name "unconnected-(U31-REFIN(+)-Pad5)") (class "Default")
      (node (ref "U31") (pin "5") (pinfunction "REFIN(+)_5") (pintype "passive+no_connect"))
    )
    (net (code "97") (name "unconnected-(U31-REFIN(-)-Pad6)") (class "Default")
      (node (ref "U31") (pin "6") (pinfunction "REFIN(-)_6") (pintype "passive+no_connect"))
    )
    (net (code "98") (name "unconnected-(U31-VIN(+)-Pad11)") (class "Default")
      (node (ref "U31") (pin "11") (pinfunction "VIN(+)_11") (pintype "passive+no_connect"))
    )
    (net (code "99") (name "unconnected-(U31-VIN(-)-Pad12)") (class "Default")
      (node (ref "U31") (pin "12") (pinfunction "VIN(-)_12") (pintype "passive+no_connect"))
    )
  )
)
